# Columns.net
KiCad netlist of a schematic drawn in Altium Designer
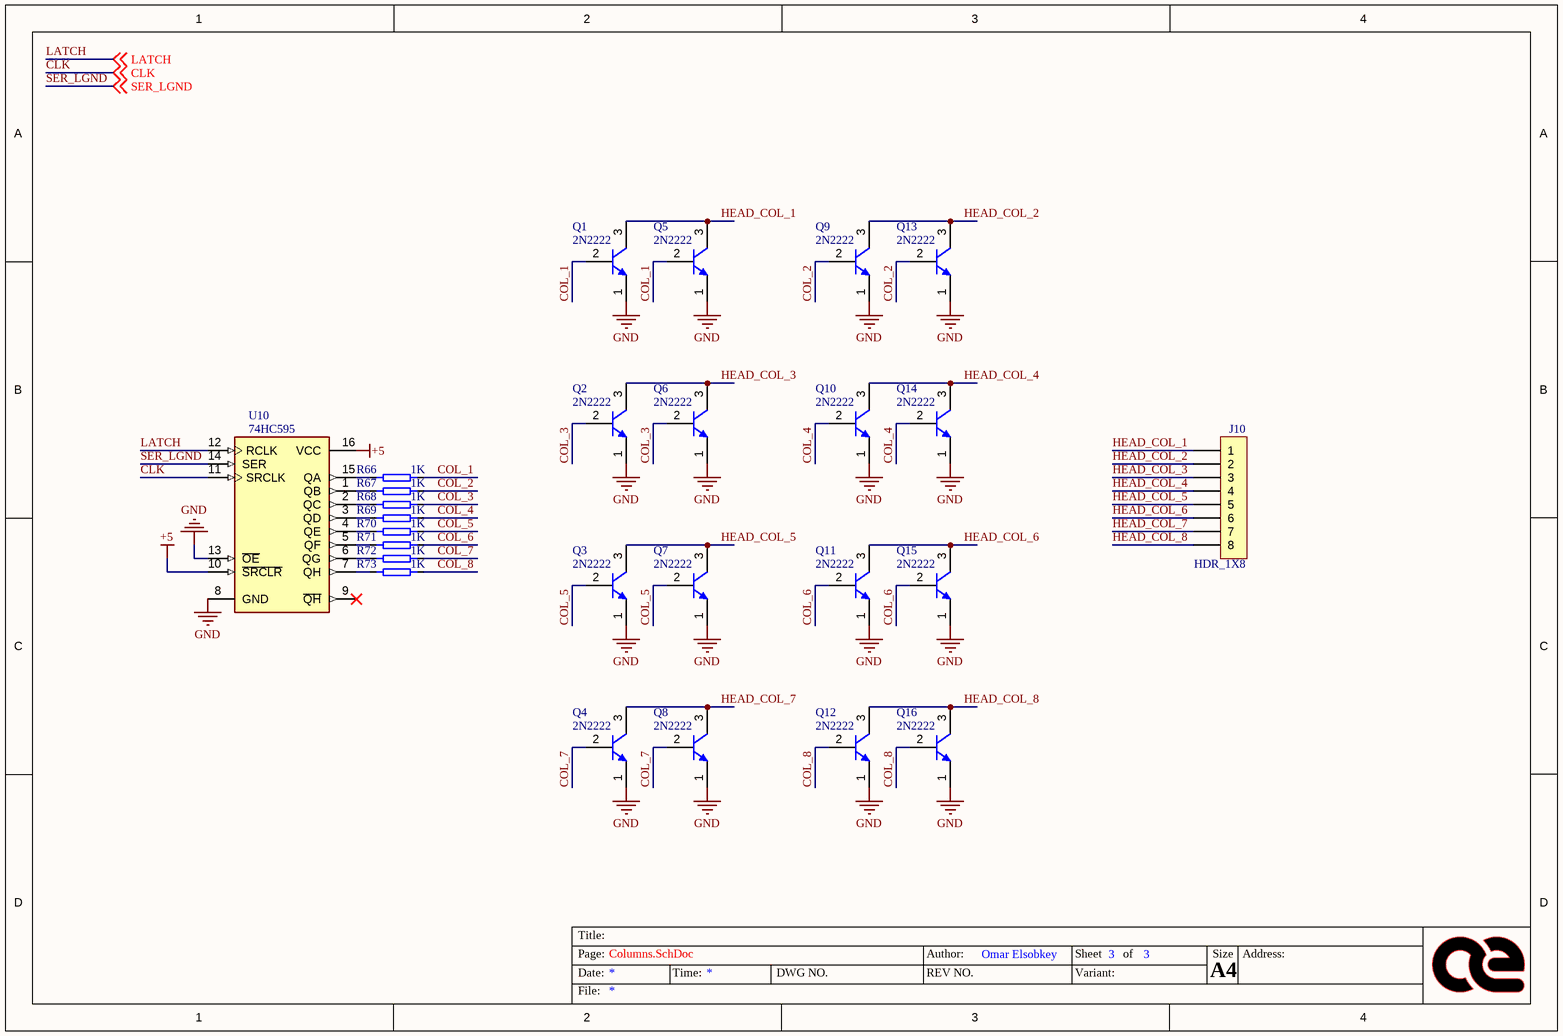
[diagram p0: Columns.SchDoc]

(export (version "E")
  (design (tool "Eeschema 10.0.6"))
  (components
    (comp (ref "J10")
      (value "HDR_1X8")
      (footprint "HDR_1X8_2.54MM")
      (description "Male Hedader 1x8")
      (libsource (lib "LED Cube") (part "HDR_1X8"))
    )
    (comp (ref "Q1")
      (value "2N2222")
      (footprint "TO92_WIDE")
      (description "Amplifier Transistor, NPN Silicon, 3-Pin TO-92, Pb-Free, Bulk Box")
      (fields (field (name "PARTNUMBER") "P2N2222AG") (field (name "MANUFACTURER") "On Semiconductor"))
      (libsource (lib "LED Cube") (part "2N2222"))
    )
    (comp (ref "Q2")
      (value "2N2222")
      (footprint "TO92_WIDE")
      (description "Amplifier Transistor, NPN Silicon, 3-Pin TO-92, Pb-Free, Bulk Box")
      (fields (field (name "PARTNUMBER") "P2N2222AG") (field (name "MANUFACTURER") "On Semiconductor"))
      (libsource (lib "LED Cube") (part "2N2222"))
    )
    (comp (ref "Q3")
      (value "2N2222")
      (footprint "TO92_WIDE")
      (description "Amplifier Transistor, NPN Silicon, 3-Pin TO-92, Pb-Free, Bulk Box")
      (fields (field (name "PARTNUMBER") "P2N2222AG") (field (name "MANUFACTURER") "On Semiconductor"))
      (libsource (lib "LED Cube") (part "2N2222"))
    )
    (comp (ref "Q4")
      (value "2N2222")
      (footprint "TO92_WIDE")
      (description "Amplifier Transistor, NPN Silicon, 3-Pin TO-92, Pb-Free, Bulk Box")
      (fields (field (name "PARTNUMBER") "P2N2222AG") (field (name "MANUFACTURER") "On Semiconductor"))
      (libsource (lib "LED Cube") (part "2N2222"))
    )
    (comp (ref "Q5")
      (value "2N2222")
      (footprint "TO92_WIDE")
      (description "Amplifier Transistor, NPN Silicon, 3-Pin TO-92, Pb-Free, Bulk Box")
      (fields (field (name "PARTNUMBER") "P2N2222AG") (field (name "MANUFACTURER") "On Semiconductor"))
      (libsource (lib "LED Cube") (part "2N2222"))
    )
    (comp (ref "Q6")
      (value "2N2222")
      (footprint "TO92_WIDE")
      (description "Amplifier Transistor, NPN Silicon, 3-Pin TO-92, Pb-Free, Bulk Box")
      (fields (field (name "PARTNUMBER") "P2N2222AG") (field (name "MANUFACTURER") "On Semiconductor"))
      (libsource (lib "LED Cube") (part "2N2222"))
    )
    (comp (ref "Q7")
      (value "2N2222")
      (footprint "TO92_WIDE")
      (description "Amplifier Transistor, NPN Silicon, 3-Pin TO-92, Pb-Free, Bulk Box")
      (fields (field (name "PARTNUMBER") "P2N2222AG") (field (name "MANUFACTURER") "On Semiconductor"))
      (libsource (lib "LED Cube") (part "2N2222"))
    )
    (comp (ref "Q8")
      (value "2N2222")
      (footprint "TO92_WIDE")
      (description "Amplifier Transistor, NPN Silicon, 3-Pin TO-92, Pb-Free, Bulk Box")
      (fields (field (name "PARTNUMBER") "P2N2222AG") (field (name "MANUFACTURER") "On Semiconductor"))
      (libsource (lib "LED Cube") (part "2N2222"))
    )
    (comp (ref "Q9")
      (value "2N2222")
      (footprint "TO92_WIDE")
      (description "Amplifier Transistor, NPN Silicon, 3-Pin TO-92, Pb-Free, Bulk Box")
      (fields (field (name "PARTNUMBER") "P2N2222AG") (field (name "MANUFACTURER") "On Semiconductor"))
      (libsource (lib "LED Cube") (part "2N2222"))
    )
    (comp (ref "Q10")
      (value "2N2222")
      (footprint "TO92_WIDE")
      (description "Amplifier Transistor, NPN Silicon, 3-Pin TO-92, Pb-Free, Bulk Box")
      (fields (field (name "PARTNUMBER") "P2N2222AG") (field (name "MANUFACTURER") "On Semiconductor"))
      (libsource (lib "LED Cube") (part "2N2222"))
    )
    (comp (ref "Q11")
      (value "2N2222")
      (footprint "TO92_WIDE")
      (description "Amplifier Transistor, NPN Silicon, 3-Pin TO-92, Pb-Free, Bulk Box")
      (fields (field (name "PARTNUMBER") "P2N2222AG") (field (name "MANUFACTURER") "On Semiconductor"))
      (libsource (lib "LED Cube") (part "2N2222"))
    )
    (comp (ref "Q12")
      (value "2N2222")
      (footprint "TO92_WIDE")
      (description "Amplifier Transistor, NPN Silicon, 3-Pin TO-92, Pb-Free, Bulk Box")
      (fields (field (name "PARTNUMBER") "P2N2222AG") (field (name "MANUFACTURER") "On Semiconductor"))
      (libsource (lib "LED Cube") (part "2N2222"))
    )
    (comp (ref "Q13")
      (value "2N2222")
      (footprint "TO92_WIDE")
      (description "Amplifier Transistor, NPN Silicon, 3-Pin TO-92, Pb-Free, Bulk Box")
      (fields (field (name "PARTNUMBER") "P2N2222AG") (field (name "MANUFACTURER") "On Semiconductor"))
      (libsource (lib "LED Cube") (part "2N2222"))
    )
    (comp (ref "Q14")
      (value "2N2222")
      (footprint "TO92_WIDE")
      (description "Amplifier Transistor, NPN Silicon, 3-Pin TO-92, Pb-Free, Bulk Box")
      (fields (field (name "PARTNUMBER") "P2N2222AG") (field (name "MANUFACTURER") "On Semiconductor"))
      (libsource (lib "LED Cube") (part "2N2222"))
    )
    (comp (ref "Q15")
      (value "2N2222")
      (footprint "TO92_WIDE")
      (description "Amplifier Transistor, NPN Silicon, 3-Pin TO-92, Pb-Free, Bulk Box")
      (fields (field (name "PARTNUMBER") "P2N2222AG") (field (name "MANUFACTURER") "On Semiconductor"))
      (libsource (lib "LED Cube") (part "2N2222"))
    )
    (comp (ref "Q16")
      (value "2N2222")
      (footprint "TO92_WIDE")
      (description "Amplifier Transistor, NPN Silicon, 3-Pin TO-92, Pb-Free, Bulk Box")
      (fields (field (name "PARTNUMBER") "P2N2222AG") (field (name "MANUFACTURER") "On Semiconductor"))
      (libsource (lib "LED Cube") (part "2N2222"))
    )
    (comp (ref "R66") (value "1K") (footprint "R_AXIAL_0.3MM") (libsource (lib "LED Cube") (part "R 1K")))
    (comp (ref "R67") (value "1K") (footprint "R_AXIAL_0.3MM") (libsource (lib "LED Cube") (part "R 1K")))
    (comp (ref "R68") (value "1K") (footprint "R_AXIAL_0.3MM") (libsource (lib "LED Cube") (part "R 1K")))
    (comp (ref "R69") (value "1K") (footprint "R_AXIAL_0.3MM") (libsource (lib "LED Cube") (part "R 1K")))
    (comp (ref "R70") (value "1K") (footprint "R_AXIAL_0.3MM") (libsource (lib "LED Cube") (part "R 1K")))
    (comp (ref "R71") (value "1K") (footprint "R_AXIAL_0.3MM") (libsource (lib "LED Cube") (part "R 1K")))
    (comp (ref "R72") (value "1K") (footprint "R_AXIAL_0.3MM") (libsource (lib "LED Cube") (part "R 1K")))
    (comp (ref "R73") (value "1K") (footprint "R_AXIAL_0.3MM") (libsource (lib "LED Cube") (part "R 1K")))
    (comp (ref "U10")
      (value "74HC595")
      (footprint "DIP16")
      (description "Shift Register 74595")
      (fields (field (name "MP") "CD74HC595E"))
      (libsource (lib "LED Cube") (part "74HC595"))
    )
  )
  (nets
    (net (code "1") (name "+5") (class "Default")
      (node (ref "U10") (pin "10") (pinfunction "~{SRCLR}_10") (pintype "input"))
      (node (ref "U10") (pin "16") (pinfunction "VCC_16") (pintype "power_in"))
    )
    (net (code "2") (name "/COL_1") (class "Default")
      (node (ref "Q1") (pin "2") (pinfunction "B_2") (pintype "passive"))
      (node (ref "Q5") (pin "2") (pinfunction "B_2") (pintype "passive"))
      (node (ref "R66") (pin "2") (pinfunction "2_2") (pintype "passive"))
    )
    (net (code "3") (name "/COL_2") (class "Default")
      (node (ref "Q13") (pin "2") (pinfunction "B_2") (pintype "passive"))
      (node (ref "Q9") (pin "2") (pinfunction "B_2") (pintype "passive"))
      (node (ref "R67") (pin "2") (pinfunction "2_2") (pintype "passive"))
    )
    (net (code "4") (name "/COL_3") (class "Default")
      (node (ref "Q2") (pin "2") (pinfunction "B_2") (pintype "passive"))
      (node (ref "Q6") (pin "2") (pinfunction "B_2") (pintype "passive"))
      (node (ref "R68") (pin "2") (pinfunction "2_2") (pintype "passive"))
    )
    (net (code "5") (name "/COL_4") (class "Default")
      (node (ref "Q10") (pin "2") (pinfunction "B_2") (pintype "passive"))
      (node (ref "Q14") (pin "2") (pinfunction "B_2") (pintype "passive"))
      (node (ref "R69") (pin "2") (pinfunction "2_2") (pintype "passive"))
    )
    (net (code "6") (name "/COL_5") (class "Default")
      (node (ref "Q3") (pin "2") (pinfunction "B_2") (pintype "passive"))
      (node (ref "Q7") (pin "2") (pinfunction "B_2") (pintype "passive"))
      (node (ref "R70") (pin "2") (pinfunction "2_2") (pintype "passive"))
    )
    (net (code "7") (name "/COL_6") (class "Default")
      (node (ref "Q11") (pin "2") (pinfunction "B_2") (pintype "passive"))
      (node (ref "Q15") (pin "2") (pinfunction "B_2") (pintype "passive"))
      (node (ref "R71") (pin "2") (pinfunction "2_2") (pintype "passive"))
    )
    (net (code "8") (name "/COL_7") (class "Default")
      (node (ref "Q4") (pin "2") (pinfunction "B_2") (pintype "passive"))
      (node (ref "Q8") (pin "2") (pinfunction "B_2") (pintype "passive"))
      (node (ref "R72") (pin "2") (pinfunction "2_2") (pintype "passive"))
    )
    (net (code "9") (name "/COL_8") (class "Default")
      (node (ref "Q12") (pin "2") (pinfunction "B_2") (pintype "passive"))
      (node (ref "Q16") (pin "2") (pinfunction "B_2") (pintype "passive"))
      (node (ref "R73") (pin "2") (pinfunction "2_2") (pintype "passive"))
    )
    (net (code "10") (name "/HEAD_COL_1") (class "Default")
      (node (ref "J10") (pin "1") (pinfunction "1_1") (pintype "passive"))
      (node (ref "Q1") (pin "3") (pinfunction "C_3") (pintype "passive"))
      (node (ref "Q5") (pin "3") (pinfunction "C_3") (pintype "passive"))
    )
    (net (code "11") (name "/HEAD_COL_2") (class "Default")
      (node (ref "J10") (pin "2") (pinfunction "2_2") (pintype "passive"))
      (node (ref "Q13") (pin "3") (pinfunction "C_3") (pintype "passive"))
      (node (ref "Q9") (pin "3") (pinfunction "C_3") (pintype "passive"))
    )
    (net (code "12") (name "/HEAD_COL_3") (class "Default")
      (node (ref "J10") (pin "3") (pinfunction "3_3") (pintype "passive"))
      (node (ref "Q2") (pin "3") (pinfunction "C_3") (pintype "passive"))
      (node (ref "Q6") (pin "3") (pinfunction "C_3") (pintype "passive"))
    )
    (net (code "13") (name "/HEAD_COL_4") (class "Default")
      (node (ref "J10") (pin "4") (pinfunction "4_4") (pintype "passive"))
      (node (ref "Q10") (pin "3") (pinfunction "C_3") (pintype "passive"))
      (node (ref "Q14") (pin "3") (pinfunction "C_3") (pintype "passive"))
    )
    (net (code "14") (name "/HEAD_COL_5") (class "Default")
      (node (ref "J10") (pin "5") (pinfunction "5_5") (pintype "passive"))
      (node (ref "Q3") (pin "3") (pinfunction "C_3") (pintype "passive"))
      (node (ref "Q7") (pin "3") (pinfunction "C_3") (pintype "passive"))
    )
    (net (code "15") (name "/HEAD_COL_6") (class "Default")
      (node (ref "J10") (pin "6") (pinfunction "6_6") (pintype "passive"))
      (node (ref "Q11") (pin "3") (pinfunction "C_3") (pintype "passive"))
      (node (ref "Q15") (pin "3") (pinfunction "C_3") (pintype "passive"))
    )
    (net (code "16") (name "/HEAD_COL_7") (class "Default")
      (node (ref "J10") (pin "7") (pinfunction "7_7") (pintype "passive"))
      (node (ref "Q4") (pin "3") (pinfunction "C_3") (pintype "passive"))
      (node (ref "Q8") (pin "3") (pinfunction "C_3") (pintype "passive"))
    )
    (net (code "17") (name "/HEAD_COL_8") (class "Default")
      (node (ref "J10") (pin "8") (pinfunction "8_8") (pintype "passive"))
      (node (ref "Q12") (pin "3") (pinfunction "C_3") (pintype "passive"))
      (node (ref "Q16") (pin "3") (pinfunction "C_3") (pintype "passive"))
    )
    (net (code "18") (name "CLK") (class "Default")
      (node (ref "U10") (pin "11") (pinfunction "SRCLK_11") (pintype "input"))
    )
    (net (code "19") (name "GND") (class "Default")
      (node (ref "Q1") (pin "1") (pinfunction "E_1") (pintype "passive"))
      (node (ref "Q10") (pin "1") (pinfunction "E_1") (pintype "passive"))
      (node (ref "Q11") (pin "1") (pinfunction "E_1") (pintype "passive"))
      (node (ref "Q12") (pin "1") (pinfunction "E_1") (pintype "passive"))
      (node (ref "Q13") (pin "1") (pinfunction "E_1") (pintype "passive"))
      (node (ref "Q14") (pin "1") (pinfunction "E_1") (pintype "passive"))
      (node (ref "Q15") (pin "1") (pinfunction "E_1") (pintype "passive"))
      (node (ref "Q16") (pin "1") (pinfunction "E_1") (pintype "passive"))
      (node (ref "Q2") (pin "1") (pinfunction "E_1") (pintype "passive"))
      (node (ref "Q3") (pin "1") (pinfunction "E_1") (pintype "passive"))
      (node (ref "Q4") (pin "1") (pinfunction "E_1") (pintype "passive"))
      (node (ref "Q5") (pin "1") (pinfunction "E_1") (pintype "passive"))
      (node (ref "Q6") (pin "1") (pinfunction "E_1") (pintype "passive"))
      (node (ref "Q7") (pin "1") (pinfunction "E_1") (pintype "passive"))
      (node (ref "Q8") (pin "1") (pinfunction "E_1") (pintype "passive"))
      (node (ref "Q9") (pin "1") (pinfunction "E_1") (pintype "passive"))
      (node (ref "U10") (pin "13") (pinfunction "~{OE}_13") (pintype "input"))
      (node (ref "U10") (pin "8") (pinfunction "GND_8") (pintype "power_in"))
    )
    (net (code "20") (name "LATCH") (class "Default")
      (node (ref "U10") (pin "12") (pinfunction "RCLK_12") (pintype "input"))
    )
    (net (code "21") (name "Net-(U10-QA)") (class "Default")
      (node (ref "R66") (pin "1") (pinfunction "1_1") (pintype "passive"))
      (node (ref "U10") (pin "15") (pinfunction "QA_15") (pintype "output"))
    )
    (net (code "22") (name "Net-(U10-QB)") (class "Default")
      (node (ref "R67") (pin "1") (pinfunction "1_1") (pintype "passive"))
      (node (ref "U10") (pin "1") (pinfunction "QB_1") (pintype "output"))
    )
    (net (code "23") (name "Net-(U10-QC)") (class "Default")
      (node (ref "R68") (pin "1") (pinfunction "1_1") (pintype "passive"))
      (node (ref "U10") (pin "2") (pinfunction "QC_2") (pintype "output"))
    )
    (net (code "24") (name "Net-(U10-QD)") (class "Default")
      (node (ref "R69") (pin "1") (pinfunction "1_1") (pintype "passive"))
      (node (ref "U10") (pin "3") (pinfunction "QD_3") (pintype "output"))
    )
    (net (code "25") (name "Net-(U10-QE)") (class "Default")
      (node (ref "R70") (pin "1") (pinfunction "1_1") (pintype "passive"))
      (node (ref "U10") (pin "4") (pinfunction "QE_4") (pintype "output"))
    )
    (net (code "26") (name "Net-(U10-QF)") (class "Default")
      (node (ref "R71") (pin "1") (pinfunction "1_1") (pintype "passive"))
      (node (ref "U10") (pin "5") (pinfunction "QF_5") (pintype "output"))
    )
    (net (code "27") (name "Net-(U10-QG)") (class "Default")
      (node (ref "R72") (pin "1") (pinfunction "1_1") (pintype "passive"))
      (node (ref "U10") (pin "6") (pinfunction "QG_6") (pintype "output"))
    )
    (net (code "28") (name "Net-(U10-QH)") (class "Default")
      (node (ref "R73") (pin "1") (pinfunction "1_1") (pintype "passive"))
      (node (ref "U10") (pin "7") (pinfunction "QH_7") (pintype "output"))
    )
    (net (code "29") (name "SER_LGND") (class "Default")
      (node (ref "U10") (pin "14") (pinfunction "SER_14") (pintype "input"))
    )
    (net (code "30") (name "unconnected-(U10-~{QH}-Pad9)") (class "Default")
      (node (ref "U10") (pin "9") (pinfunction "~{QH}_9") (pintype "output+no_connect"))
    )
  )
)
